# Schematic_DC_PowerSupply.net
KiCad netlist of a schematic drawn in Altium Designer
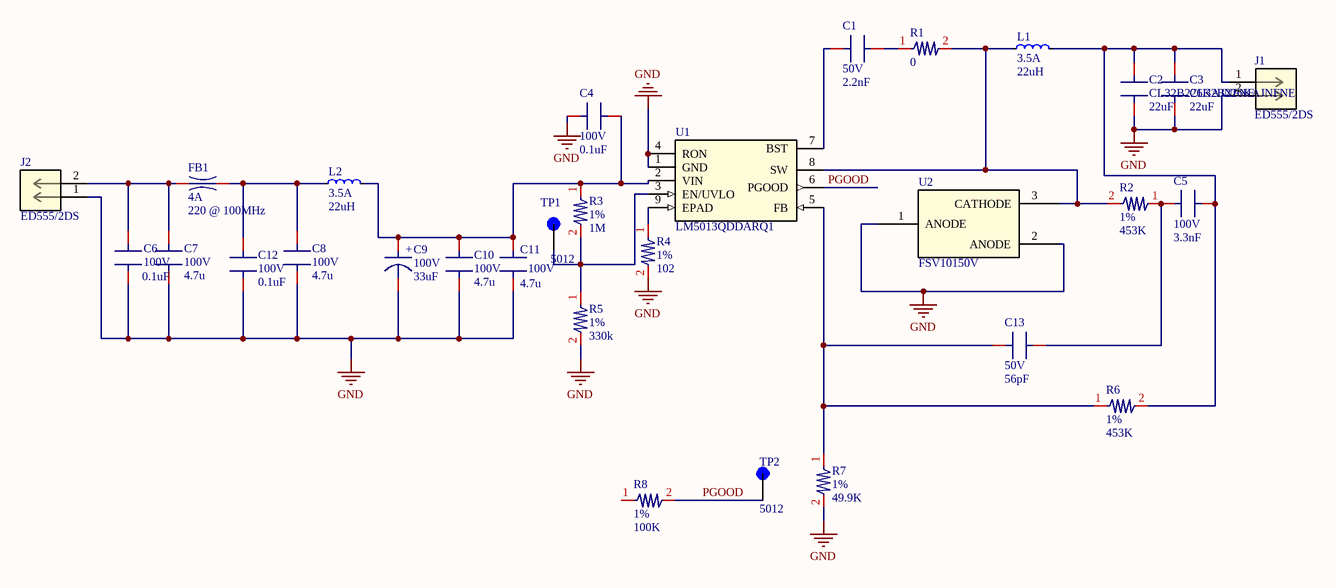
[diagram p0: Schematic_DC_PowerSupply.SchDoc]

(export (version "E")
  (design (tool "Eeschema 10.0.6"))
  (components
    (comp (ref "C1")
      (value "2.2nF")
      (footprint "CAP_1608_TDK")
      (description "CAP CER 2.2nF 50V X7R 1005")
      (fields
        (field (name "PART NUMBER") "66-000203")
        (field (name "TOLERANCE") "10%")
        (field (name "RATING") "50V")
      )
      (libsource (lib "Schlib1") (part "CAP-1005-2.7nF-10%-50V"))
    )
    (comp (ref "C2")
      (value "CL32B226KAJNFNE")
      (footprint "CAP_CL32_SAM")
      (description "CAP CER 22uF 20% 25V X5R 3235 (1210)")
      (fields
        (field (name "PART NUMBER") "66-000233")
        (field (name "TOLERANCE") "20%")
        (field (name "ALTIUM_VALUE") "22uF")
        (field (name "CREATED BY") "VG")
      )
      (libsource (lib "Schlib1") (part "CAP-3225-22uFF-20%-25V"))
    )
    (comp (ref "C3")
      (value "CL32B226KAJNFNE")
      (footprint "CAP_CL32_SAM")
      (description "CAP CER 22uF 20% 25V X5R 3235 (1210)")
      (fields
        (field (name "PART NUMBER") "66-000233")
        (field (name "TOLERANCE") "20%")
        (field (name "ALTIUM_VALUE") "22uF")
        (field (name "CREATED BY") "VG")
      )
      (libsource (lib "Schlib1") (part "CAP-3225-22uFF-20%-25V"))
    )
    (comp (ref "C4")
      (value "0.1uF")
      (footprint "HMK107_TAY")
      (description "Ceramic,0.1uF, 100V,10%,X7S, 1608,SMD")
      (fields
        (field (name "PART NUMBER") "66-000086")
        (field (name "TOLERANCE") "10%")
        (field (name "RATING") "100V")
        (field (name "CREATED BY") "Wayne")
      )
      (libsource (lib "ASI_SCH_LIB") (part "CAP-1608-0.1uF-10%-100V"))
    )
    (comp (ref "C5")
      (value "3.3nF")
      (footprint "CAP_1608_TDK")
      (description "CAP CER 3300PF (3n3) 100V 10% X7R 1608")
      (fields
        (field (name "PART NUMBER") "66-000160")
        (field (name "TOLERANCE") "10%")
        (field (name "RATING") "100V")
        (field (name "CREATED BY") "Wayne")
      )
      (libsource (lib "Schlib1") (part "CAP-1608-3300pF-10%-100V"))
    )
    (comp (ref "C6")
      (value "0.1uF")
      (footprint "CAP_SMD_10P3X10P3_PAN")
      (description "Ceramic,0.1uF, 100V,10%,X7S, 1608,SMD")
      (fields
        (field (name "PART NUMBER") "66-000086")
        (field (name "TOLERANCE") "10%")
        (field (name "RATING") "100V")
        (field (name "CREATED BY") "Wayne")
      )
      (libsource (lib "") (part "CAP-1608-0.1uF-10%-100V_1"))
    )
    (comp (ref "C7")
      (value "4.7u")
      (footprint "CAP_3225_TDK")
      (description "CAP 3225 X7R 100V 4.7UF 10% 2.50")
      (fields
        (field (name "PART NUMBER") "66-000252")
        (field (name "TOLERANCE") "10%")
        (field (name "RATING") "100V")
        (field (name "CREATED BY") "Akshat Doctor")
      )
      (libsource (lib "ASI_SCH_LIB") (part "CAP-3225-4.7uF-10%-100V"))
    )
    (comp (ref "C8")
      (value "4.7u")
      (footprint "CAP_3225_TDK")
      (description "CAP 3225 X7R 100V 4.7UF 10% 2.50")
      (fields
        (field (name "PART NUMBER") "66-000252")
        (field (name "TOLERANCE") "10%")
        (field (name "RATING") "100V")
        (field (name "CREATED BY") "Akshat Doctor")
      )
      (libsource (lib "ASI_SCH_LIB") (part "CAP-3225-4.7uF-10%-100V"))
    )
    (comp (ref "C9")
      (value "33uF")
      (footprint "HMK107_TAY")
      (description "CAP POLY 33UF 40mOhm 100V 20% SMD")
      (fields
        (field (name "PART NUMBER") "660-000305")
        (field (name "TOLERANCE") "20%")
        (field (name "RATING") "100V")
        (field (name "CREATED BY") "VG")
      )
      (libsource (lib "ASI_SCH_LIB") (part "CAP-100127-33uF-20%-100V"))
    )
    (comp (ref "C10")
      (value "4.7u")
      (footprint "CAP_3225_TDK")
      (description "CAP 3225 X7R 100V 4.7UF 10% 2.50")
      (fields
        (field (name "PART NUMBER") "66-000252")
        (field (name "TOLERANCE") "10%")
        (field (name "RATING") "100V")
        (field (name "CREATED BY") "Akshat Doctor")
      )
      (libsource (lib "ASI_SCH_LIB") (part "CAP-3225-4.7uF-10%-100V"))
    )
    (comp (ref "C11")
      (value "4.7u")
      (footprint "HMK107_TAY")
      (description "CAP 3225 X7R 100V 4.7UF 10% 2.50")
      (fields
        (field (name "PART NUMBER") "66-000252")
        (field (name "TOLERANCE") "10%")
        (field (name "RATING") "100V")
        (field (name "CREATED BY") "Akshat Doctor")
      )
      (libsource (lib "ASI_SCH_LIB") (part "CAP-3225-4.7uF-10%-100V"))
    )
    (comp (ref "C12")
      (value "0.1uF")
      (footprint "CAP_0402C_AVX")
      (description "Ceramic,0.1uF, 100V,10%,X7S, 1608,SMD")
      (fields
        (field (name "PART NUMBER") "66-000086")
        (field (name "TOLERANCE") "10%")
        (field (name "RATING") "100V")
        (field (name "CREATED BY") "Wayne")
      )
      (libsource (lib "ASI_SCH_LIB") (part "CAP-1608-0.1uF-10%-100V"))
    )
    (comp (ref "C13")
      (value "56pF")
      (footprint "RESC1005X04N")
      (description "CAP CER 56pF 50V C0G 1005")
      (fields
        (field (name "PART NUMBER") "66-000260")
        (field (name "TOLERANCE") "5%")
        (field (name "RATING") "50V")
        (field (name "CREATED BY") "Vlad Geyts")
      )
      (libsource (lib "ASI_SCH_LIB") (part "CAP-1005-47pF-5%-50V"))
    )
    (comp (ref "FB1")
      (value "220 @ 100MHz")
      (footprint "BEADC3216X180N")
      (description "FERRITE CHIP 220 OHM 4A 1206")
      (fields
        (field (name "PART NUMBER") "58-000026")
        (field (name "TOLERANCE") "NA")
        (field (name "RATING") "4A")
        (field (name "CREATED BY") "Wayne")
      )
      (libsource (lib "Schlib1") (part "FB-1206-220-4A-FBMH3216HM221NTV"))
    )
    (comp (ref "J1")
      (value "ED555/2DS")
      (footprint "CONN_ED5552DS_OST")
      (description "Terminal Block, 3.5mm, 2x1")
      (fields (field (name "COPYRIGHT") "Copyright (C) 2023 Ultra Librarian. All rights reserved."))
      (libsource (lib "") (part "ED5552DS_1_1"))
    )
    (comp (ref "J2")
      (value "ED555/2DS")
      (footprint "CONN_ED5552DS_OST")
      (description "Terminal Block, 3.5mm, 2x1")
      (fields (field (name "COPYRIGHT") "Copyright (C) 2023 Ultra Librarian. All rights reserved."))
      (libsource (lib "Schlib2") (part "ED5552DS_1"))
    )
    (comp (ref "L1")
      (value "22uH")
      (footprint "IND_1040-WE-LHMI_WRE")
      (description "SHIELDED FIXED IND 22uH 3.5A 74mohm SM")
      (fields
        (field (name "PART NUMBER") "58-000127")
        (field (name "TOLERANCE") "20%")
        (field (name "RATING") "3.5A")
        (field (name "CREATED BY") "Akshat Doctor")
      )
      (libsource (lib "Schlib1") (part "IND-7373-270uH-20%-0.43A"))
    )
    (comp (ref "L2")
      (value "22uH")
      (footprint "IND_1040-WE-LHMI_WRE")
      (description "SHIELDED FIXED IND 22uH 3.5A 74mohm SM")
      (fields
        (field (name "PART NUMBER") "58-000127")
        (field (name "TOLERANCE") "20%")
        (field (name "RATING") "3.5A")
        (field (name "CREATED BY") "Akshat Doctor")
      )
      (libsource (lib "Schlib1") (part "IND-7373-270uH-20%-0.43A"))
    )
    (comp (ref "R1")
      (value "0")
      (footprint "RESC1005X04N")
      (description "0, 1%, 1005, SMD")
      (fields
        (field (name "PART NUMBER") "60-000402")
        (field (name "TOLERANCE") "1%")
        (field (name "CREATED BY") "VG")
      )
      (libsource (lib "ASI_SCH_LIB") (part "RES-1005-49.9K-1%-55V-1/16W"))
    )
    (comp (ref "R2")
      (value "453K")
      (footprint "RC0603N_YAG")
      (description "475K, 1%, 1608, SMD")
      (fields
        (field (name "PART NUMBER") "60-000071")
        (field (name "TOLERANCE") "1%")
        (field (name "Comment") "RC0603FR-07453KL")
        (field (name "CREATED BY") "Wayne")
      )
      (libsource (lib "ASI_SCH_LIB") (part "RES-1608-475K-1%-200V-1/10W"))
    )
    (comp (ref "R3")
      (value "1M")
      (footprint "RES_CRCW_0402")
      (description "1M, 1%, 1005, SMD")
      (fields
        (field (name "PART NUMBER") "60-000346")
        (field (name "TOLERANCE") "1%")
        (field (name "Comment") "CRCW04021M00FKED")
        (field (name "CREATED BY") "VG")
      )
      (libsource (lib "ASI_SCH_LIB") (part "RES-1005-1M-1%-50V-1/16W"))
    )
    (comp (ref "R4")
      (value "102")
      (footprint "RES_CRCW_0402")
      (description "102 ohm, 1%, 1005, SMD")
      (fields
        (field (name "PART NUMBER") "60-000346")
        (field (name "TOLERANCE") "1%")
        (field (name "Comment") "CRCW0402330KFKED")
        (field (name "CREATED BY") "VG")
      )
      (libsource (lib "ASI_SCH_LIB") (part "RES-1005-1M-1%-50V-1/16W"))
    )
    (comp (ref "R5")
      (value "330k")
      (footprint "RC0603N_YAG")
      (description "330k, 1%, 1005, SMD")
      (fields
        (field (name "PART NUMBER") "60-000346")
        (field (name "TOLERANCE") "1%")
        (field (name "Comment") "RC0603FR-07453KL")
        (field (name "CREATED BY") "VG")
      )
      (libsource (lib "ASI_SCH_LIB") (part "RES-1005-1M-1%-50V-1/16W"))
    )
    (comp (ref "R6")
      (value "453K")
      (footprint "RES_CRCW_0402")
      (description "453K, 1%, 1608, SMD")
      (fields
        (field (name "PART NUMBER") "60-000071")
        (field (name "TOLERANCE") "1%")
        (field (name "Comment") "CRCW040249K9FKED")
        (field (name "CREATED BY") "Wayne")
      )
      (libsource (lib "Schlib1") (part "RES-1608-475K-1%-200V-1/10W"))
    )
    (comp (ref "R7")
      (value "49.9K")
      (footprint "RES_1005_SAM")
      (description "49.9K, 1%, 1005, SMD")
      (fields
        (field (name "PART NUMBER") "60-000508")
        (field (name "TOLERANCE") "1%")
        (field (name "Comment") "RC1005F104CS")
        (field (name "CREATED BY") "Vlad  Geyts")
      )
      (libsource (lib "Schlib1") (part "RES-1005-475K-1%-50V-1/16W"))
    )
    (comp (ref "R8")
      (value "100K")
      (footprint "RESC1005X04N")
      (description "100K, 1%, 1005, SMD")
      (fields
        (field (name "PART NUMBER") "60-000508")
        (field (name "TOLERANCE") "1%")
        (field (name "CREATED BY") "Vlad  Geyts")
      )
      (libsource (lib "Schlib1") (part "RES-1005-475K-1%-50V-1/16W"))
    )
    (comp (ref "TP1") (value "5012") (footprint "TP_5012") (libsource (lib "Schlib2") (part "5012")))
    (comp (ref "TP2") (value "5012") (footprint "TP_5012") (libsource (lib "Schlib2") (part "5012")))
    (comp (ref "U1")
      (value "LM5013QDDARQ1")
      (footprint "POWERPAD8_DDA_TEX")
      (description "U_LM5013_100V_Buck_Converter")
      (fields (field (name "COPYRIGHT") "Copyright (C) 2023 Ultra Librarian. All rights reserved."))
      (libsource (lib "LM5013QDDARQ1") (part "LM5013QDDARQ1"))
    )
    (comp (ref "U2")
      (value "FSV10150V")
      (footprint "TO277-3L_ONS")
      (description "Schottkey Diode, 150V, 10A, 3-Pin")
      (fields (field (name "COPYRIGHT") "Copyright (C) 2023 Ultra Librarian. All rights reserved."))
      (libsource (lib "Schlib2") (part "FSV10150V_1"))
    )
  )
  (nets
    (net (code "1") (name "/PGOOD") (class "Default")
      (node (ref "R8") (pin "2") (pinfunction "2_2") (pintype "passive"))
      (node (ref "TP2") (pin "TP") (pinfunction "TP_TP") (pintype "passive"))
      (node (ref "U1") (pin "6") (pinfunction "PGOOD_6") (pintype "output"))
    )
    (net (code "2") (name "GND") (class "Default")
      (node (ref "C10") (pin "1") (pinfunction "1_1") (pintype "passive"))
      (node (ref "C11") (pin "1") (pinfunction "1_1") (pintype "passive"))
      (node (ref "C12") (pin "2") (pinfunction "2_2") (pintype "passive"))
      (node (ref "C2") (pin "1") (pinfunction "1_1") (pintype "passive"))
      (node (ref "C3") (pin "1") (pinfunction "1_1") (pintype "passive"))
      (node (ref "C4") (pin "1") (pinfunction "1_1") (pintype "passive"))
      (node (ref "C6") (pin "1") (pinfunction "1_1") (pintype "passive"))
      (node (ref "C7") (pin "1") (pinfunction "1_1") (pintype "passive"))
      (node (ref "C8") (pin "1") (pinfunction "1_1") (pintype "passive"))
      (node (ref "C9") (pin "1") (pinfunction "1_1") (pintype "passive"))
      (node (ref "J1") (pin "2") (pinfunction "2_2") (pintype "passive"))
      (node (ref "J2") (pin "1") (pinfunction "1_1") (pintype "passive"))
      (node (ref "R4") (pin "2") (pinfunction "2_2") (pintype "passive"))
      (node (ref "R5") (pin "2") (pinfunction "2_2") (pintype "passive"))
      (node (ref "R7") (pin "2") (pinfunction "2_2") (pintype "passive"))
      (node (ref "U1") (pin "1") (pinfunction "GND_1") (pintype "power_in"))
      (node (ref "U1") (pin "4") (pinfunction "RON_4") (pintype "power_in"))
      (node (ref "U2") (pin "1") (pinfunction "ANODE_1") (pintype "passive"))
      (node (ref "U2") (pin "2") (pinfunction "ANODE_2") (pintype "passive"))
    )
    (net (code "3") (name "Net-(C1-Pad2)") (class "Default")
      (node (ref "C1") (pin "2") (pinfunction "2_2") (pintype "passive"))
      (node (ref "R1") (pin "1") (pinfunction "1_1") (pintype "passive"))
    )
    (net (code "4") (name "Net-(C2-Pad2)") (class "Default")
      (node (ref "C2") (pin "2") (pinfunction "2_2") (pintype "passive"))
      (node (ref "C3") (pin "2") (pinfunction "2_2") (pintype "passive"))
      (node (ref "C5") (pin "2") (pinfunction "2_2") (pintype "passive"))
      (node (ref "J1") (pin "1") (pinfunction "1_1") (pintype "passive"))
      (node (ref "L1") (pin "1") (pinfunction "1_1") (pintype "passive"))
      (node (ref "R6") (pin "2") (pinfunction "2_2") (pintype "passive"))
    )
    (net (code "5") (name "Net-(C6-Pad1)") (class "Default")
      (node (ref "C6") (pin "1") (pinfunction "1_1") (pintype "passive"))
      (node (ref "C7") (pin "1") (pinfunction "1_1") (pintype "passive"))
      (node (ref "FB1") (pin "1") (pinfunction "1_1") (pintype "passive"))
      (node (ref "J2") (pin "2") (pinfunction "2_2") (pintype "passive"))
    )
    (net (code "6") (name "Net-(C12-Pad1)") (class "Default")
      (node (ref "C12") (pin "1") (pinfunction "1_1") (pintype "passive"))
      (node (ref "C8") (pin "1") (pinfunction "1_1") (pintype "passive"))
      (node (ref "FB1") (pin "2") (pinfunction "2_2") (pintype "passive"))
      (node (ref "L2") (pin "2") (pinfunction "2_2") (pintype "passive"))
    )
    (net (code "7") (name "Net-(C13-Pad2)") (class "Default")
      (node (ref "C13") (pin "2") (pinfunction "2_2") (pintype "passive"))
      (node (ref "C5") (pin "1") (pinfunction "1_1") (pintype "passive"))
      (node (ref "R2") (pin "1") (pinfunction "1_1") (pintype "passive"))
    )
    (net (code "8") (name "Net-(U1-BST)") (class "Default")
      (node (ref "C1") (pin "1") (pinfunction "1_1") (pintype "passive"))
      (node (ref "U1") (pin "7") (pinfunction "BST_7") (pintype "power_in"))
    )
    (net (code "9") (name "Net-(U1-EN{slash}UVLO)") (class "Default")
      (node (ref "R3") (pin "2") (pinfunction "2_2") (pintype "passive"))
      (node (ref "R5") (pin "1") (pinfunction "1_1") (pintype "passive"))
      (node (ref "TP1") (pin "TP") (pinfunction "TP_TP") (pintype "passive"))
      (node (ref "U1") (pin "3") (pinfunction "EN/UVLO_3") (pintype "input"))
    )
    (net (code "10") (name "Net-(U1-EPAD)") (class "Default")
      (node (ref "R4") (pin "1") (pinfunction "1_1") (pintype "passive"))
      (node (ref "U1") (pin "9") (pinfunction "EPAD_9") (pintype "input"))
    )
    (net (code "11") (name "Net-(U1-FB)") (class "Default")
      (node (ref "C13") (pin "1") (pinfunction "1_1") (pintype "passive"))
      (node (ref "R6") (pin "1") (pinfunction "1_1") (pintype "passive"))
      (node (ref "R7") (pin "1") (pinfunction "1_1") (pintype "passive"))
      (node (ref "U1") (pin "5") (pinfunction "FB_5") (pintype "input"))
    )
    (net (code "12") (name "Net-(U1-SW)") (class "Default")
      (node (ref "L1") (pin "2") (pinfunction "2_2") (pintype "passive"))
      (node (ref "R1") (pin "2") (pinfunction "2_2") (pintype "passive"))
      (node (ref "R2") (pin "2") (pinfunction "2_2") (pintype "passive"))
      (node (ref "U1") (pin "8") (pinfunction "SW_8") (pintype "power_in"))
      (node (ref "U2") (pin "3") (pinfunction "CATHODE_3") (pintype "passive"))
    )
    (net (code "13") (name "Net-(U1-VIN)") (class "Default")
      (node (ref "C10") (pin "1") (pinfunction "1_1") (pintype "passive"))
      (node (ref "C11") (pin "1") (pinfunction "1_1") (pintype "passive"))
      (node (ref "C4") (pin "2") (pinfunction "2_2") (pintype "passive"))
      (node (ref "C9") (pin "1") (pinfunction "1_1") (pintype "passive"))
      (node (ref "L2") (pin "1") (pinfunction "1_1") (pintype "passive"))
      (node (ref "R3") (pin "1") (pinfunction "1_1") (pintype "passive"))
      (node (ref "U1") (pin "2") (pinfunction "VIN_2") (pintype "power_in"))
    )
    (net (code "14") (name "unconnected-(R8-Pad1)") (class "Default")
      (node (ref "R8") (pin "1") (pinfunction "1_1") (pintype "passive"))
    )
  )
)
